# USB_Phy.net
KiCad netlist of a schematic drawn in Altium Designer
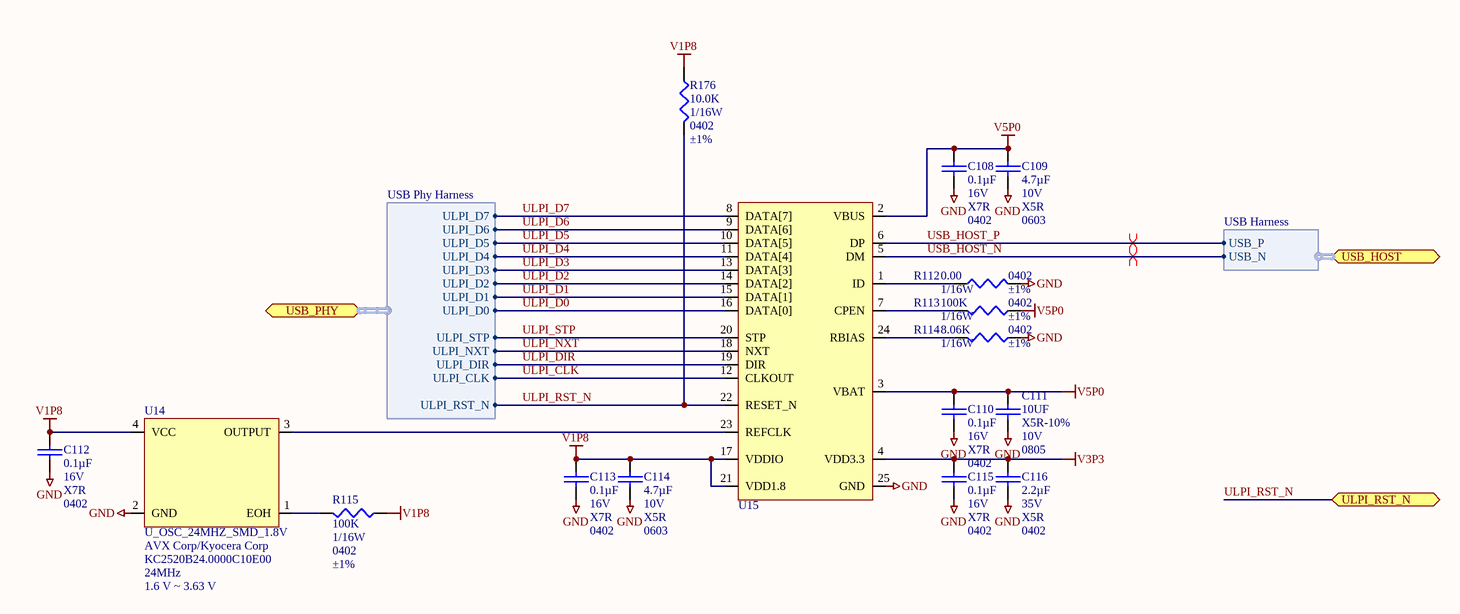
[diagram p0: USB Phy.SchDoc]

(export (version "E")
  (design (tool "Eeschema 10.0.6"))
  (components
    (comp (ref "C108")
      (value "0.1uF")
      (footprint "C_0402")
      (description "CAP CER .10UF 16V X7R 0402")
      (fields
        (field (name "MANUFACTURER") "Murata Electronics North America")
        (field (name "MANUFACTURER PART NUMBER") "GRM155R71C104KA88J")
        (field (name "CAPACITANCE") "0.1µF")
        (field (name "VOLTAGE - RATED") "16V")
        (field (name "TEMPERATURE COEFFICIENT") "X7R")
        (field (name "PACKAGE / CASE") "0402")
      )
      (libsource (lib "Main LibraryX") (part "C_0402_0.1UF_16V"))
    )
    (comp (ref "C109")
      (value "4.7µF")
      (footprint "C_ERA-0603")
      (description "CAP CER 4.7UF 10V X5R 0603")
      (fields
        (field (name "MANUFACTURER") "Murata Electronics North America")
        (field (name "MANUFACTURER PART NUMBER") "GRM188R61A475KE15D")
        (field (name "CAPACITANCE") "4.7µF")
        (field (name "VOLTAGE - RATED") "10V")
        (field (name "TEMPERATURE COEFFICIENT") "X5R")
        (field (name "PACKAGE / CASE") "0603")
      )
      (libsource (lib "Main LibraryX") (part "C_0603_4.7uF_10V"))
    )
    (comp (ref "C110")
      (value "0.1uF")
      (footprint "C_0402")
      (description "CAP CER .10UF 16V X7R 0402")
      (fields
        (field (name "MANUFACTURER") "Murata Electronics North America")
        (field (name "MANUFACTURER PART NUMBER") "GRM155R71C104KA88J")
        (field (name "CAPACITANCE") "0.1µF")
        (field (name "VOLTAGE - RATED") "16V")
        (field (name "TEMPERATURE COEFFICIENT") "X7R")
        (field (name "PACKAGE / CASE") "0402")
      )
      (libsource (lib "Main LibraryX") (part "C_0402_0.1UF_16V"))
    )
    (comp (ref "C111")
      (value "10UF")
      (footprint "0805")
      (description "CAP CER 10UF 10V 10% X5R 0805")
      (fields
        (field (name "MANUFACTURER") "Murata Electronics North America")
        (field (name "MANUFACTURER PART NUMBER") "GRM21BR61A106KE19L")
        (field (name "TOLERANCE") "X5R-10%")
        (field (name "VOLTS") "10V")
      )
      (libsource (lib "Main Library") (part "C_0805_10UF_10V"))
    )
    (comp (ref "C112")
      (value "0.1uF")
      (footprint "C_0402")
      (description "CAP CER .10UF 16V X7R 0402")
      (fields
        (field (name "MANUFACTURER") "Murata Electronics North America")
        (field (name "MANUFACTURER PART NUMBER") "GRM155R71C104KA88J")
        (field (name "CAPACITANCE") "0.1µF")
        (field (name "VOLTAGE - RATED") "16V")
        (field (name "TEMPERATURE COEFFICIENT") "X7R")
        (field (name "PACKAGE / CASE") "0402")
      )
      (libsource (lib "Main LibraryX") (part "C_0402_0.1UF_16V"))
    )
    (comp (ref "C113")
      (value "0.1uF")
      (footprint "C_0402")
      (description "CAP CER .10UF 16V X7R 0402")
      (fields
        (field (name "MANUFACTURER") "Murata Electronics North America")
        (field (name "MANUFACTURER PART NUMBER") "GRM155R71C104KA88J")
        (field (name "CAPACITANCE") "0.1µF")
        (field (name "VOLTAGE - RATED") "16V")
        (field (name "TEMPERATURE COEFFICIENT") "X7R")
        (field (name "PACKAGE / CASE") "0402")
      )
      (libsource (lib "Main LibraryX") (part "C_0402_0.1UF_16V"))
    )
    (comp (ref "C114")
      (value "4.7µF")
      (footprint "C_ERA-0603")
      (description "CAP CER 4.7UF 10V X5R 0603")
      (fields
        (field (name "MANUFACTURER") "Murata Electronics North America")
        (field (name "MANUFACTURER PART NUMBER") "GRM188R61A475KE15D")
        (field (name "CAPACITANCE") "4.7µF")
        (field (name "VOLTAGE - RATED") "10V")
        (field (name "TEMPERATURE COEFFICIENT") "X5R")
        (field (name "PACKAGE / CASE") "0603")
      )
      (libsource (lib "Main LibraryX") (part "C_0603_4.7uF_10V"))
    )
    (comp (ref "C115")
      (value "0.1uF")
      (footprint "C_0402")
      (description "CAP CER .10UF 16V X7R 0402")
      (fields
        (field (name "MANUFACTURER") "Murata Electronics North America")
        (field (name "MANUFACTURER PART NUMBER") "GRM155R71C104KA88J")
        (field (name "CAPACITANCE") "0.1µF")
        (field (name "VOLTAGE - RATED") "16V")
        (field (name "TEMPERATURE COEFFICIENT") "X7R")
        (field (name "PACKAGE / CASE") "0402")
      )
      (libsource (lib "Main LibraryX") (part "C_0402_0.1UF_16V"))
    )
    (comp (ref "C116")
      (value "C_0402_2.2uF_35V")
      (footprint "C_ERA-0402")
      (description "CAP CER 2.2UF 35V 20% X5R 0402")
      (fields
        (field (name "MANUFACTURER") "TDK Corporation")
        (field (name "MANUFACTURER PART NUMBER") "C1005X5R1V225K050BC")
        (field (name "CAPACITANCE") "2.2µF")
        (field (name "VOLTAGE - RATED") "35V")
        (field (name "TEMPERATURE COEFFICIENT") "X5R")
        (field (name "PACKAGE / CASE") "0402")
      )
      (libsource (lib "Main LibraryX") (part "C_0402_2.2uF_35V"))
    )
    (comp (ref "R112")
      (value "0.0 Ohms")
      (footprint "R_0402")
      (description "RES SMD 0.0OHM JUMPER 1/10W 0402")
      (fields
        (field (name "MANUFACTURER") "Panasonic - ECG")
        (field (name "MANUFACTURER PART NUMBER") "ERJ-2GE0R00X")
        (field (name "RESISTANCE IN OHMS") "0.00")
        (field (name "POWER (WATTS)") "1/16W")
        (field (name "CASE") "0402")
        (field (name "TOLERANCE") "±1%")
      )
      (libsource (lib "Main LibraryX") (part "R_0402_0.00"))
    )
    (comp (ref "R113")
      (value "R_0402_100K")
      (footprint "R_0402")
      (description "RES SMD 100K OHM 1% 1/16W 0402")
      (fields
        (field (name "MANUFACTURER") "Yageo")
        (field (name "MANUFACTURER PART NUMBER") "RC0402FR-07100KL")
        (field (name "RESISTANCE IN OHMS") "100K")
        (field (name "POWER (WATTS)") "1/16W")
        (field (name "CASE") "0402")
        (field (name "TOLERANCE") "±1%")
      )
      (libsource (lib "Cospan Design") (part "R_0402_100K"))
    )
    (comp (ref "R114")
      (value "R_0402_8.06K")
      (footprint "R_0402")
      (description "RES 8.06K OHM 1/16W 1% 0402 SMD")
      (fields
        (field (name "MANUFACTURER") "Yageo")
        (field (name "MANUFACTURER PART NUMBER") "RC0402FR-078K06L")
        (field (name "RESISTANCE IN OHMS") "8.06K")
        (field (name "POWER (WATTS)") "1/16W")
        (field (name "CASE") "0402")
        (field (name "TOLERANCE") "±1%")
      )
      (libsource (lib "Main Library") (part "R_0402_8.06K"))
    )
    (comp (ref "R115")
      (value "R_0402_100K")
      (footprint "R_0402")
      (description "RES SMD 100K OHM 1% 1/16W 0402")
      (fields
        (field (name "MANUFACTURER") "Yageo")
        (field (name "MANUFACTURER PART NUMBER") "RC0402FR-07100KL")
        (field (name "RESISTANCE IN OHMS") "100K")
        (field (name "POWER (WATTS)") "1/16W")
        (field (name "CASE") "0402")
        (field (name "TOLERANCE") "±1%")
      )
      (libsource (lib "Cospan Design") (part "R_0402_100K"))
    )
    (comp (ref "R176")
      (value "R_0402_10.0K")
      (footprint "R_0402")
      (description "RES 10.0K OHM 1/16W 1% 0402 SMD")
      (fields
        (field (name "MANUFACTURER") "Stackpole Electronics Inc")
        (field (name "MANUFACTURER PART NUMBER") "RMCF0402FT10K0")
        (field (name "RESISTANCE IN OHMS") "10.0K")
        (field (name "POWER (WATTS)") "1/16W")
        (field (name "CASE") "0402")
        (field (name "TOLERANCE") "±1%")
      )
      (libsource (lib "Main Library") (part "R_0402_10.0K"))
    )
    (comp (ref "U14")
      (value "U_OSC_24MHZ_SMD_1.8V")
      (footprint "OSC_KC5032A")
      (description "24MHz CMOS XO (Standard) Oscillator")
      (fields
        (field (name "MANUFACTURER") "AVX Corp/Kyocera Corp")
        (field (name "MANUFACTURER PART NUMBER") "KC2520B24.0000C10E00")
        (field (name "FREQUENCY") "24MHz")
        (field (name "VOLTAGE - SUPPLY") "1.6 V ~ 3.63 V")
      )
      (libsource (lib "Cospan Design") (part "U_OSC_24MHZ_SMD_1.8V"))
    )
    (comp (ref "U15")
      (value "U_USB3315C")
      (footprint "QFN50P400X400X100_HS-25N")
      (description "IC TXRX USB FLEXPWR 24QFN")
      (fields
        (field (name "MANUFACTURER") "Microchip Technology")
        (field (name "MANUFACTURER PART NUMBER") "USB3315C-CP-TR")
      )
      (libsource (lib "Cospan Design") (part "U_USB3315C"))
    )
  )
  (nets
    (net (code "4") (name "/ULPI_CLK") (class "Default")
      (node (ref "U15") (pin "12") (pinfunction "CLKOUT_12") (pintype "passive"))
    )
    (net (code "5") (name "/ULPI_D0") (class "Default")
      (node (ref "U15") (pin "16") (pinfunction "DATA[0]_16") (pintype "passive"))
    )
    (net (code "6") (name "/ULPI_D1") (class "Default")
      (node (ref "U15") (pin "15") (pinfunction "DATA[1]_15") (pintype "passive"))
    )
    (net (code "7") (name "/ULPI_D2") (class "Default")
      (node (ref "U15") (pin "14") (pinfunction "DATA[2]_14") (pintype "passive"))
    )
    (net (code "8") (name "/ULPI_D3") (class "Default")
      (node (ref "U15") (pin "13") (pinfunction "DATA[3]_13") (pintype "passive"))
    )
    (net (code "9") (name "/ULPI_D4") (class "Default")
      (node (ref "U15") (pin "11") (pinfunction "DATA[4]_11") (pintype "passive"))
    )
    (net (code "10") (name "/ULPI_D5") (class "Default")
      (node (ref "U15") (pin "10") (pinfunction "DATA[5]_10") (pintype "passive"))
    )
    (net (code "11") (name "/ULPI_D6") (class "Default")
      (node (ref "U15") (pin "9") (pinfunction "DATA[6]_9") (pintype "passive"))
    )
    (net (code "12") (name "/ULPI_D7") (class "Default")
      (node (ref "U15") (pin "8") (pinfunction "DATA[7]_8") (pintype "passive"))
    )
    (net (code "13") (name "/ULPI_DIR") (class "Default")
      (node (ref "U15") (pin "19") (pinfunction "DIR_19") (pintype "passive"))
    )
    (net (code "14") (name "/ULPI_NXT") (class "Default")
      (node (ref "U15") (pin "18") (pinfunction "NXT_18") (pintype "passive"))
    )
    (net (code "15") (name "/ULPI_RST_N") (class "Default")
      (node (ref "R176") (pin "1") (pinfunction "1_1") (pintype "passive"))
      (node (ref "U15") (pin "22") (pinfunction "RESET_N_22") (pintype "passive"))
    )
    (net (code "16") (name "/ULPI_STP") (class "Default")
      (node (ref "U15") (pin "20") (pinfunction "STP_20") (pintype "passive"))
    )
    (net (code "17") (name "/USB_HOST_N") (class "Default")
      (node (ref "U15") (pin "5") (pinfunction "DM_5") (pintype "passive"))
    )
    (net (code "18") (name "/USB_HOST_P") (class "Default")
      (node (ref "U15") (pin "6") (pinfunction "DP_6") (pintype "passive"))
    )
    (net (code "21") (name "GND") (class "Default")
      (node (ref "C108") (pin "1") (pinfunction "1_1") (pintype "passive"))
      (node (ref "C109") (pin "1") (pinfunction "1_1") (pintype "passive"))
      (node (ref "C110") (pin "1") (pinfunction "1_1") (pintype "passive"))
      (node (ref "C111") (pin "1") (pinfunction "1_1") (pintype "passive"))
      (node (ref "C112") (pin "1") (pinfunction "1_1") (pintype "passive"))
      (node (ref "C113") (pin "1") (pinfunction "1_1") (pintype "passive"))
      (node (ref "C114") (pin "1") (pinfunction "1_1") (pintype "passive"))
      (node (ref "C115") (pin "1") (pinfunction "1_1") (pintype "passive"))
      (node (ref "C116") (pin "1") (pinfunction "1_1") (pintype "passive"))
      (node (ref "R112") (pin "1") (pinfunction "1_1") (pintype "passive"))
      (node (ref "R114") (pin "2") (pinfunction "2_2") (pintype "passive"))
      (node (ref "U14") (pin "2") (pinfunction "GND_2") (pintype "passive"))
      (node (ref "U15") (pin "25") (pinfunction "GND_25") (pintype "passive"))
    )
    (net (code "22") (name "Net-(U14-EOH)") (class "Default")
      (node (ref "R115") (pin "1") (pinfunction "1_1") (pintype "passive"))
      (node (ref "U14") (pin "1") (pinfunction "EOH_1") (pintype "passive"))
    )
    (net (code "23") (name "Net-(U14-OUTPUT)") (class "Default")
      (node (ref "U14") (pin "3") (pinfunction "OUTPUT_3") (pintype "passive"))
      (node (ref "U15") (pin "23") (pinfunction "REFCLK_23") (pintype "passive"))
    )
    (net (code "24") (name "Net-(U15-CPEN)") (class "Default")
      (node (ref "R113") (pin "1") (pinfunction "1_1") (pintype "passive"))
      (node (ref "U15") (pin "7") (pinfunction "CPEN_7") (pintype "passive"))
    )
    (net (code "25") (name "Net-(U15-ID)") (class "Default")
      (node (ref "R112") (pin "2") (pinfunction "2_2") (pintype "passive"))
      (node (ref "U15") (pin "1") (pinfunction "ID_1") (pintype "passive"))
    )
    (net (code "26") (name "Net-(U15-RBIAS)") (class "Default")
      (node (ref "R114") (pin "1") (pinfunction "1_1") (pintype "passive"))
      (node (ref "U15") (pin "24") (pinfunction "RBIAS_24") (pintype "passive"))
    )
    (net (code "27") (name "V1P8") (class "Default")
      (node (ref "C112") (pin "2") (pinfunction "2_2") (pintype "passive"))
      (node (ref "C113") (pin "2") (pinfunction "2_2") (pintype "passive"))
      (node (ref "C114") (pin "2") (pinfunction "2_2") (pintype "passive"))
      (node (ref "R115") (pin "2") (pinfunction "2_2") (pintype "passive"))
      (node (ref "R176") (pin "2") (pinfunction "2_2") (pintype "passive"))
      (node (ref "U14") (pin "4") (pinfunction "VCC_4") (pintype "passive"))
      (node (ref "U15") (pin "17") (pinfunction "VDDIO_17") (pintype "passive"))
      (node (ref "U15") (pin "21") (pinfunction "VDD1.8_21") (pintype "passive"))
    )
    (net (code "28") (name "V3P3") (class "Default")
      (node (ref "C115") (pin "2") (pinfunction "2_2") (pintype "passive"))
      (node (ref "C116") (pin "2") (pinfunction "2_2") (pintype "passive"))
      (node (ref "U15") (pin "4") (pinfunction "VDD3.3_4") (pintype "passive"))
    )
    (net (code "29") (name "V5P0") (class "Default")
      (node (ref "C108") (pin "2") (pinfunction "2_2") (pintype "passive"))
      (node (ref "C109") (pin "2") (pinfunction "2_2") (pintype "passive"))
      (node (ref "C110") (pin "2") (pinfunction "2_2") (pintype "passive"))
      (node (ref "C111") (pin "2") (pinfunction "2_2") (pintype "passive"))
      (node (ref "R113") (pin "2") (pinfunction "2_2") (pintype "passive"))
      (node (ref "U15") (pin "2") (pinfunction "VBUS_2") (pintype "passive"))
      (node (ref "U15") (pin "3") (pinfunction "VBAT_3") (pintype "passive"))
    )
  )
)
